# 477ProjectSchematic.net
KiCad netlist of a schematic drawn in EAGLE
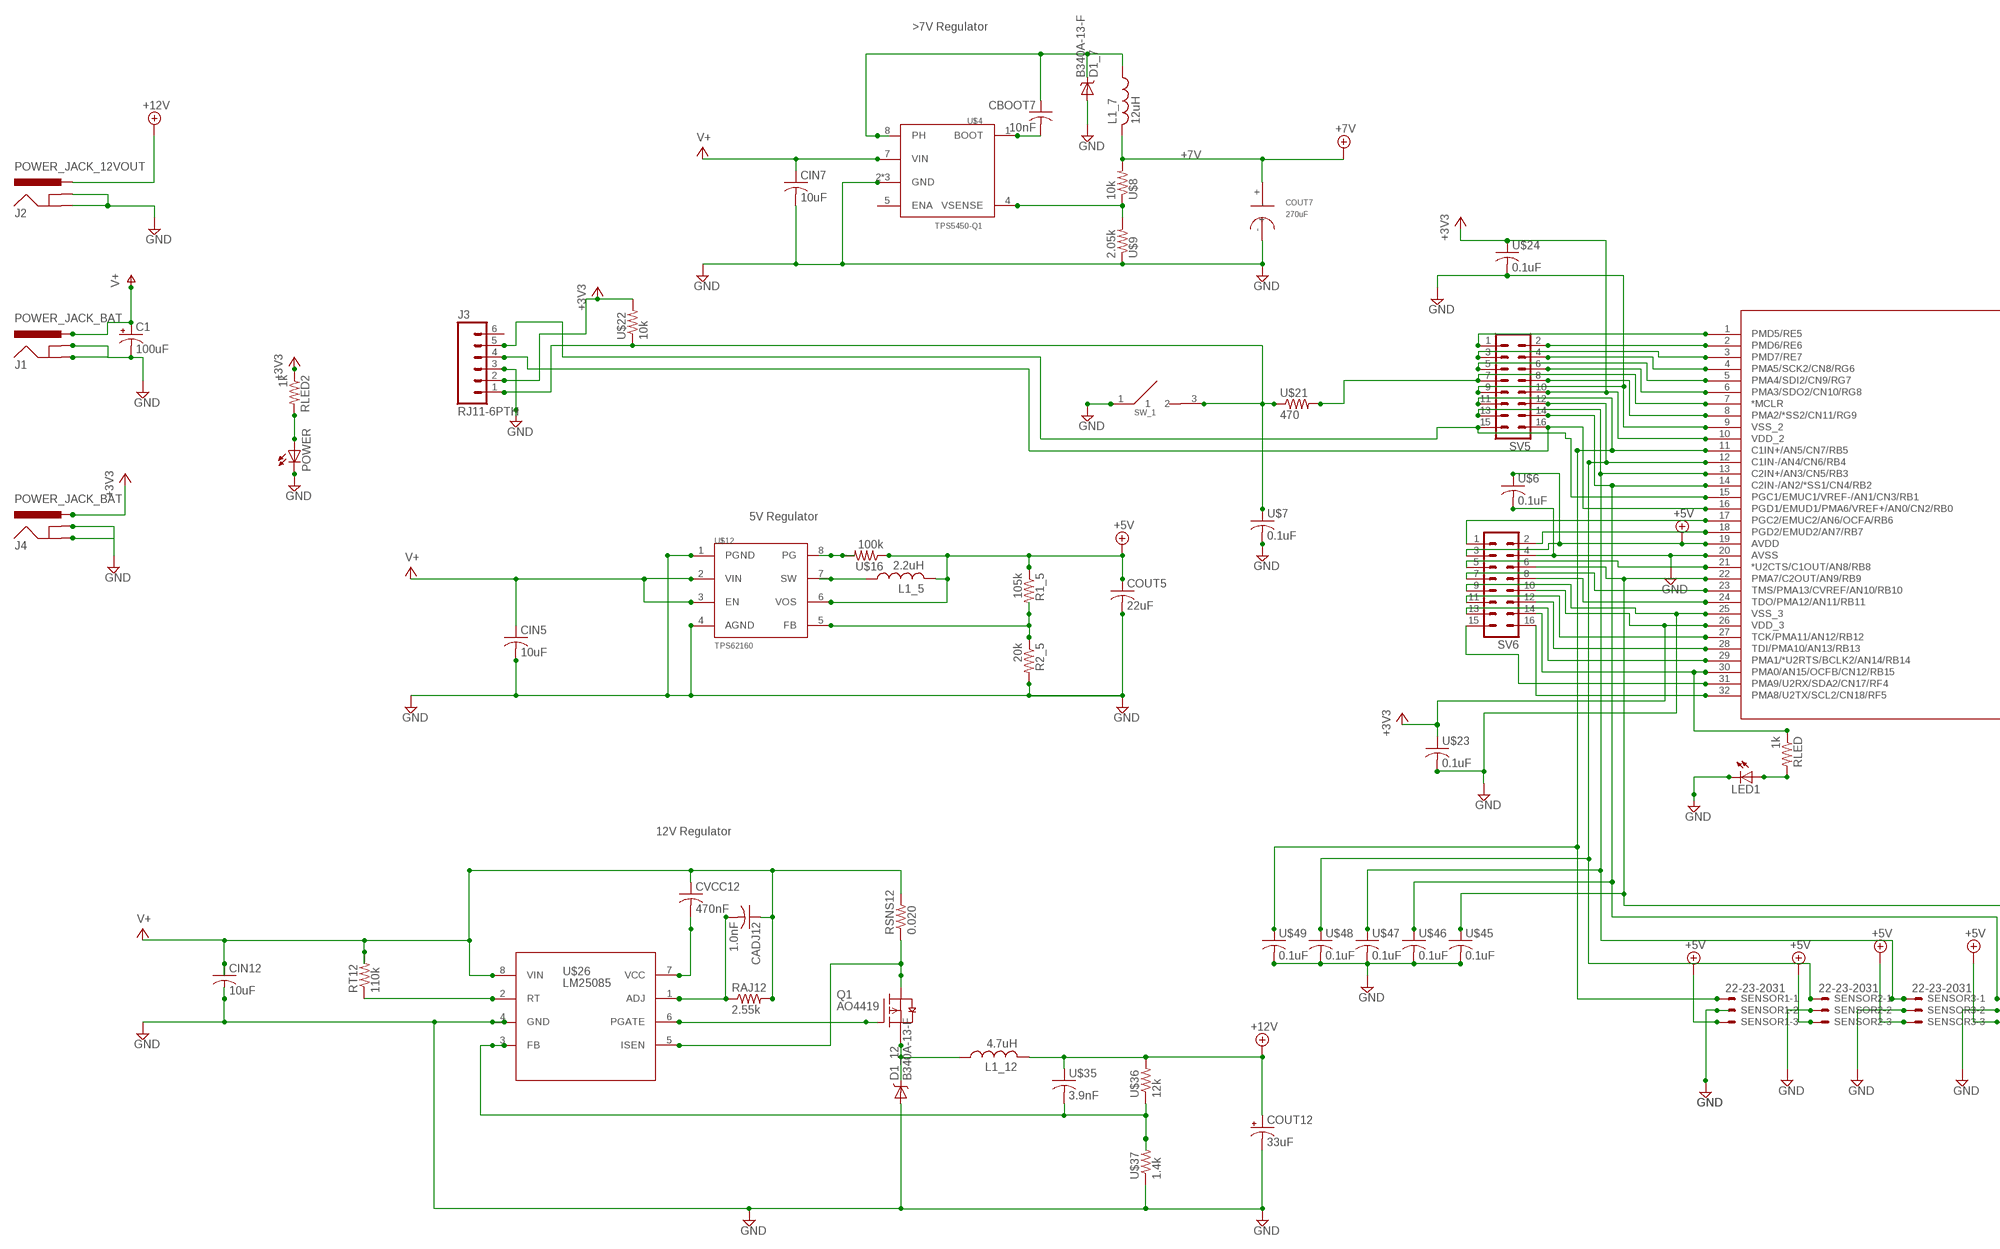
[diagram p0: schematic, sheet 1, part 1 of 2]
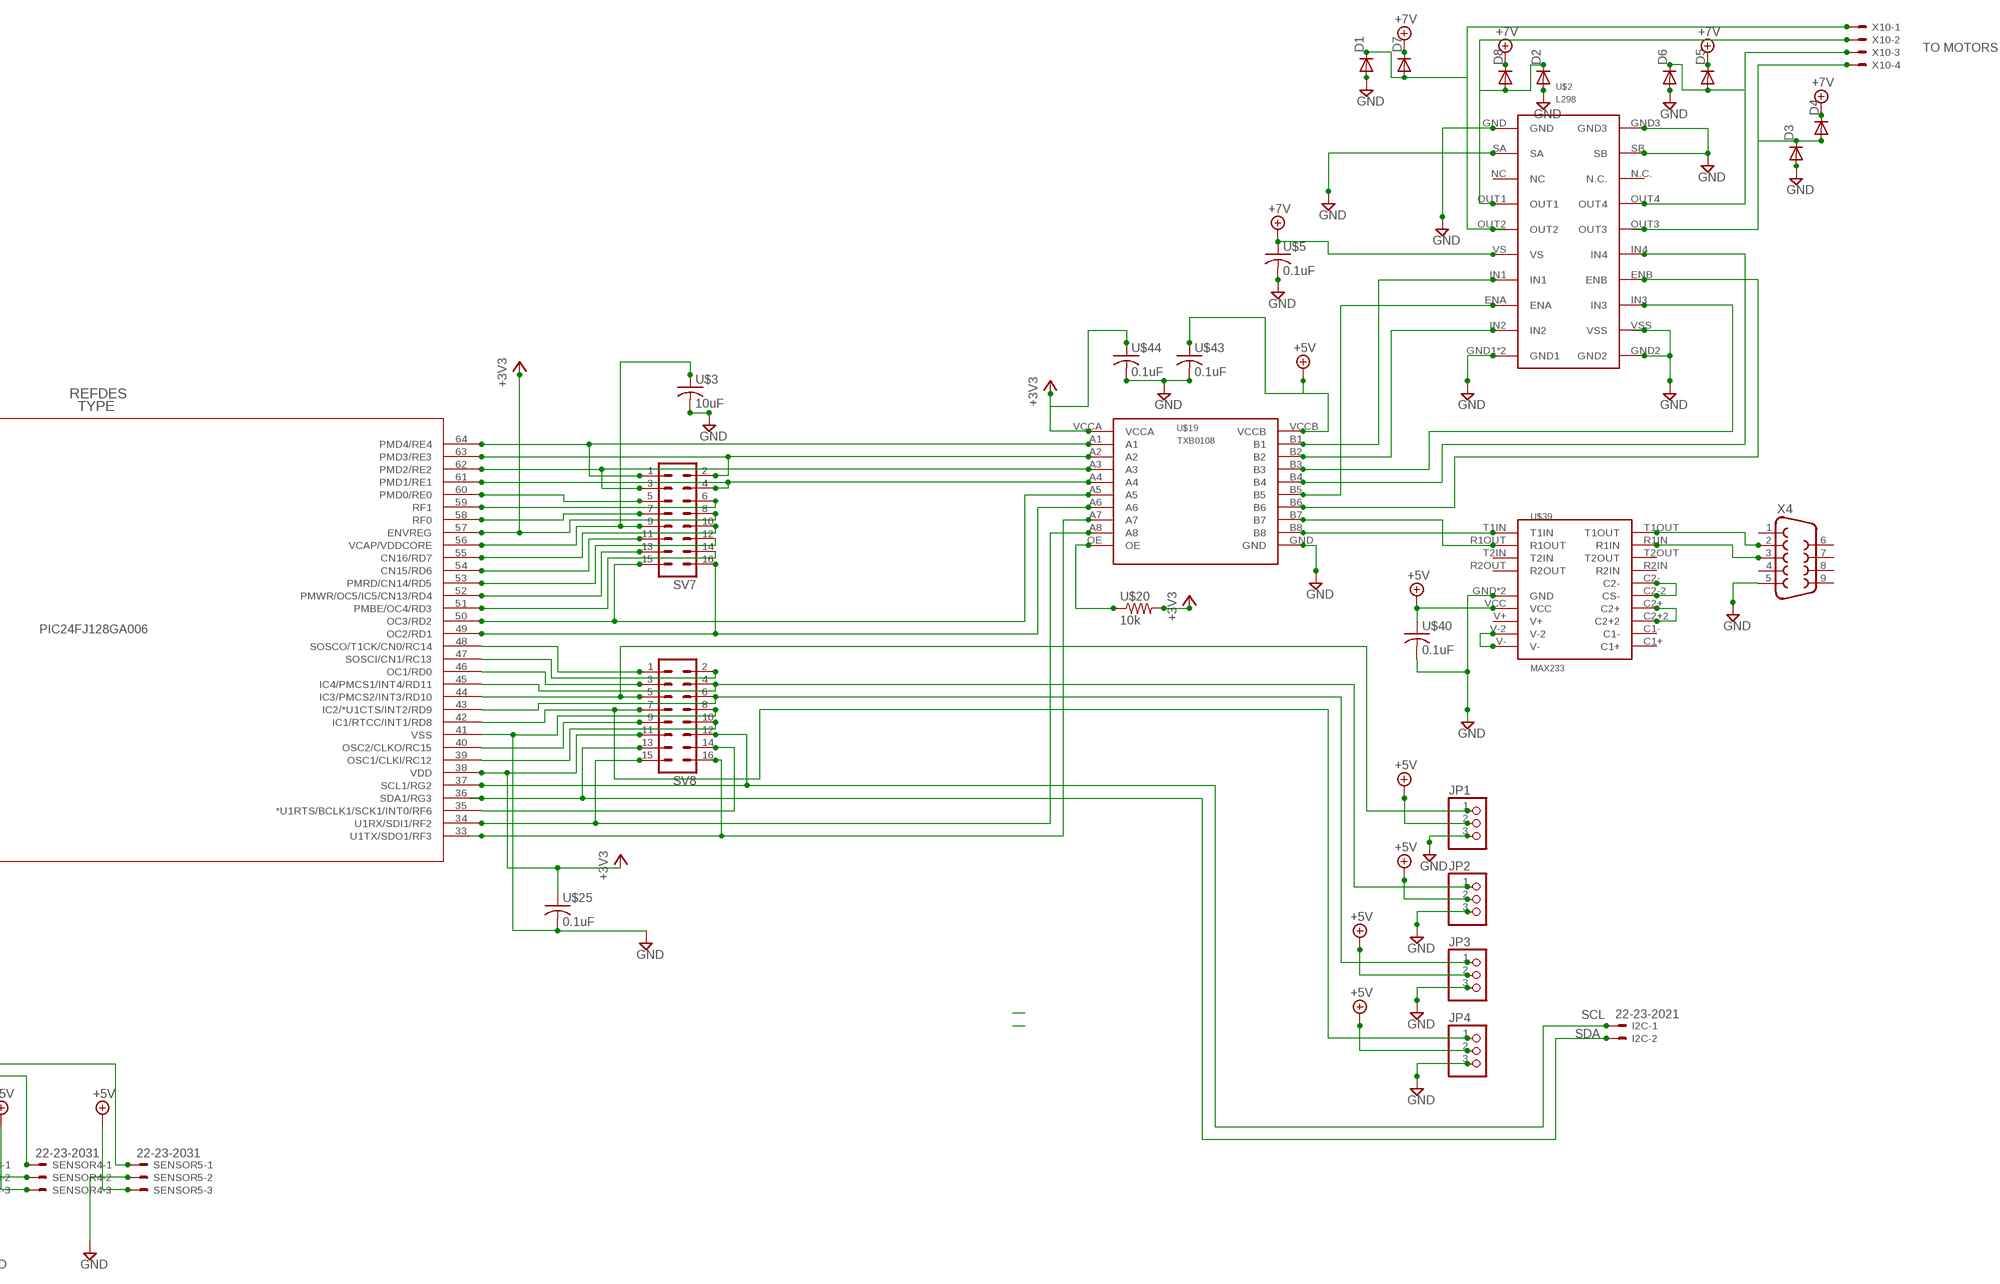
[diagram p1: schematic, sheet 1, part 2 of 2]

(export (version "E")
  (design (tool "Eeschema 10.0.6"))
  (components
    (comp (ref "C1")
      (value "100uF")
      (footprint "eagle-import:E3,5-8")
      (libsource (lib "eagle-import") (part "CPOL-USE3.5-8"))
    )
    (comp (ref "CADJ12")
      (value "1.0nF")
      (footprint "eagle-import:C1206")
      (libsource (lib "eagle-import") (part "C-US-1206"))
    )
    (comp (ref "CBOOT7")
      (value "10nF")
      (footprint "eagle-import:C1206")
      (libsource (lib "eagle-import") (part "C-US-1206"))
    )
    (comp (ref "CIN5")
      (value "10uF")
      (footprint "eagle-import:C1206")
      (libsource (lib "eagle-import") (part "C-US-1206"))
    )
    (comp (ref "CIN7")
      (value "10uF")
      (footprint "eagle-import:C1210")
      (libsource (lib "eagle-import") (part "C-US-1210"))
    )
    (comp (ref "CIN12")
      (value "10uF")
      (footprint "eagle-import:C1210")
      (libsource (lib "eagle-import") (part "C-US-1210"))
    )
    (comp (ref "COUT5")
      (value "22uF")
      (footprint "eagle-import:C1206")
      (libsource (lib "eagle-import") (part "C-US-1206"))
    )
    (comp (ref "COUT7")
      (value "270uF")
      (footprint "eagle-import:CAPSMT_62_J80")
      (libsource (lib "eagle-import") (part "APXA100ARA271MJ80G"))
    )
    (comp (ref "COUT12")
      (value "33uF")
      (footprint "eagle-import:D_7343-31W")
      (libsource (lib "eagle-import") (part "T495D336K025ATE090"))
    )
    (comp (ref "CVCC12")
      (value "470nF")
      (footprint "eagle-import:C1206")
      (libsource (lib "eagle-import") (part "C-US-1206"))
    )
    (comp (ref "D1")
      (value "DIODE-DO-214AC")
      (footprint "eagle-import:DO-214AC")
      (libsource (lib "eagle-import") (part "DIODE-DO-214AC"))
    )
    (comp (ref "D1_7")
      (value "B340A-13-F")
      (footprint "eagle-import:SMA-DIODE")
      (libsource (lib "eagle-import") (part "B340A-13-F"))
    )
    (comp (ref "D1_12")
      (value "B340A-13-F")
      (footprint "eagle-import:SMA-DIODE")
      (libsource (lib "eagle-import") (part "B340A-13-F"))
    )
    (comp (ref "D2")
      (value "DIODE-DO-214AC")
      (footprint "eagle-import:DO-214AC")
      (libsource (lib "eagle-import") (part "DIODE-DO-214AC"))
    )
    (comp (ref "D3")
      (value "DIODE-DO-214AC")
      (footprint "eagle-import:DO-214AC")
      (libsource (lib "eagle-import") (part "DIODE-DO-214AC"))
    )
    (comp (ref "D4")
      (value "DIODE-DO-214AC")
      (footprint "eagle-import:DO-214AC")
      (libsource (lib "eagle-import") (part "DIODE-DO-214AC"))
    )
    (comp (ref "D5")
      (value "DIODE-DO-214AC")
      (footprint "eagle-import:DO-214AC")
      (libsource (lib "eagle-import") (part "DIODE-DO-214AC"))
    )
    (comp (ref "D6")
      (value "DIODE-DO-214AC")
      (footprint "eagle-import:DO-214AC")
      (libsource (lib "eagle-import") (part "DIODE-DO-214AC"))
    )
    (comp (ref "D7")
      (value "DIODE-DO-214AC")
      (footprint "eagle-import:DO-214AC")
      (libsource (lib "eagle-import") (part "DIODE-DO-214AC"))
    )
    (comp (ref "D8")
      (value "DIODE-DO-214AC")
      (footprint "eagle-import:DO-214AC")
      (libsource (lib "eagle-import") (part "DIODE-DO-214AC"))
    )
    (comp (ref "I2C")
      (value "22-23-2021")
      (footprint "eagle-import:22-23-2021")
      (fields (field (name "MF") "MOLEX"))
      (libsource (lib "eagle-import") (part "22-23-2021"))
    )
    (comp (ref "J1")
      (value "POWER_JACK_BAT")
      (footprint "eagle-import:POWER_JACK_PTH")
      (libsource (lib "eagle-import") (part "POWER_JACKPTH"))
    )
    (comp (ref "J2")
      (value "POWER_JACK_12VOUT")
      (footprint "eagle-import:POWER_JACK_PTH")
      (libsource (lib "eagle-import") (part "POWER_JACKPTH"))
    )
    (comp (ref "J3")
      (value "RJ11-6PTH")
      (footprint "eagle-import:RJ11-6")
      (libsource (lib "eagle-import") (part "RJ11-6PTH"))
    )
    (comp (ref "J4")
      (value "POWER_JACK_BAT")
      (footprint "eagle-import:POWER_JACK_PTH")
      (libsource (lib "eagle-import") (part "POWER_JACKPTH"))
    )
    (comp (ref "JP1")
      (value "PINHD-1X3")
      (footprint "eagle-import:1X03")
      (libsource (lib "eagle-import") (part "PINHD-1X3"))
    )
    (comp (ref "JP2")
      (value "PINHD-1X3")
      (footprint "eagle-import:1X03")
      (libsource (lib "eagle-import") (part "PINHD-1X3"))
    )
    (comp (ref "JP3")
      (value "PINHD-1X3")
      (footprint "eagle-import:1X03")
      (libsource (lib "eagle-import") (part "PINHD-1X3"))
    )
    (comp (ref "JP4")
      (value "PINHD-1X3")
      (footprint "eagle-import:1X03")
      (libsource (lib "eagle-import") (part "PINHD-1X3"))
    )
    (comp (ref "L1_5")
      (value "2.2uH")
      (footprint "eagle-import:SDR0403")
      (libsource (lib "eagle-import") (part "SDR0403"))
    )
    (comp (ref "L1_7")
      (value "12uH")
      (footprint "eagle-import:SRR1210")
      (libsource (lib "eagle-import") (part "SRR1210"))
    )
    (comp (ref "L1_12")
      (value "4.7uH")
      (footprint "eagle-import:SLF10165")
      (libsource (lib "eagle-import") (part "SLF10165T-4R7N4R73PF"))
    )
    (comp (ref "LED1")
      (value "LEDSMT1206")
      (footprint "eagle-import:1206")
      (libsource (lib "eagle-import") (part "LEDSMT1206"))
    )
    (comp (ref "POWER")
      (value "LEDSMT1206")
      (footprint "eagle-import:1206")
      (libsource (lib "eagle-import") (part "LEDSMT1206"))
    )
    (comp (ref "Q1")
      (value "AO4419")
      (footprint "eagle-import:SOIC8")
      (libsource (lib "eagle-import") (part "AO4419"))
    )
    (comp (ref "R1_5")
      (value "105k")
      (footprint "eagle-import:R1206")
      (libsource (lib "eagle-import") (part "R-US{dblquote}"))
    )
    (comp (ref "R2_5")
      (value "20k")
      (footprint "eagle-import:R1206")
      (libsource (lib "eagle-import") (part "R-US{dblquote}"))
    )
    (comp (ref "RAJ12")
      (value "2.55k")
      (footprint "eagle-import:R1206")
      (libsource (lib "eagle-import") (part "R-US{dblquote}"))
    )
    (comp (ref "RLED")
      (value "1k")
      (footprint "eagle-import:R1206")
      (libsource (lib "eagle-import") (part "R-US{dblquote}"))
    )
    (comp (ref "RLED2")
      (value "1k")
      (footprint "eagle-import:R1206")
      (libsource (lib "eagle-import") (part "R-US{dblquote}"))
    )
    (comp (ref "RSNS12")
      (value "0.020")
      (footprint "eagle-import:R1206")
      (libsource (lib "eagle-import") (part "R-US{dblquote}"))
    )
    (comp (ref "RT12")
      (value "110k")
      (footprint "eagle-import:R1206")
      (libsource (lib "eagle-import") (part "R-US{dblquote}"))
    )
    (comp (ref "SENSOR1")
      (value "22-23-2031")
      (footprint "eagle-import:22-23-2031")
      (fields (field (name "MF") "MOLEX"))
      (libsource (lib "eagle-import") (part "22-23-2031"))
    )
    (comp (ref "SENSOR2")
      (value "22-23-2031")
      (footprint "eagle-import:22-23-2031")
      (fields (field (name "MF") "MOLEX"))
      (libsource (lib "eagle-import") (part "22-23-2031"))
    )
    (comp (ref "SENSOR3")
      (value "22-23-2031")
      (footprint "eagle-import:22-23-2031")
      (fields (field (name "MF") "MOLEX"))
      (libsource (lib "eagle-import") (part "22-23-2031"))
    )
    (comp (ref "SENSOR4")
      (value "22-23-2031")
      (footprint "eagle-import:22-23-2031")
      (fields (field (name "MF") "MOLEX"))
      (libsource (lib "eagle-import") (part "22-23-2031"))
    )
    (comp (ref "SENSOR5")
      (value "22-23-2031")
      (footprint "eagle-import:22-23-2031")
      (fields (field (name "MF") "MOLEX"))
      (libsource (lib "eagle-import") (part "22-23-2031"))
    )
    (comp (ref "SV5")
      (value "MA08-2")
      (footprint "eagle-import:MA08-2")
      (libsource (lib "eagle-import") (part "MA08-2"))
    )
    (comp (ref "SV6")
      (value "MA08-2")
      (footprint "eagle-import:MA08-2")
      (libsource (lib "eagle-import") (part "MA08-2"))
    )
    (comp (ref "SV7")
      (value "MA08-2")
      (footprint "eagle-import:MA08-2")
      (libsource (lib "eagle-import") (part "MA08-2"))
    )
    (comp (ref "SV8")
      (value "MA08-2")
      (footprint "eagle-import:MA08-2")
      (libsource (lib "eagle-import") (part "MA08-2"))
    )
    (comp (ref "SW_1")
      (value "RESET_BUTTON")
      (footprint "eagle-import:TACTILE-PTH-12MM")
      (libsource (lib "eagle-import") (part "RESET_BUTTON"))
    )
    (comp (ref "U$1")
      (value "PIC24FJ128GA006-")
      (footprint "eagle-import:TQFP64_10X10MC")
      (libsource (lib "eagle-import") (part "PIC24FJ128GA006-"))
    )
    (comp (ref "U$2")
      (value "L298")
      (footprint "eagle-import:L298")
      (libsource (lib "eagle-import") (part "L298"))
    )
    (comp (ref "U$3")
      (value "10uF")
      (footprint "eagle-import:C1206")
      (libsource (lib "eagle-import") (part "C-US-1206"))
    )
    (comp (ref "U$4")
      (value "TPS5450-Q1")
      (footprint "eagle-import:PSOP-8")
      (libsource (lib "eagle-import") (part "TPS5450-Q1"))
    )
    (comp (ref "U$5")
      (value "0.1uF")
      (footprint "eagle-import:C1206")
      (libsource (lib "eagle-import") (part "C-US-1206"))
    )
    (comp (ref "U$6")
      (value "0.1uF")
      (footprint "eagle-import:C1206")
      (libsource (lib "eagle-import") (part "C-US-1206"))
    )
    (comp (ref "U$7")
      (value "0.1uF")
      (footprint "eagle-import:C1206")
      (libsource (lib "eagle-import") (part "C-US-1206"))
    )
    (comp (ref "U$8")
      (value "10k")
      (footprint "eagle-import:R1206")
      (libsource (lib "eagle-import") (part "R-US{dblquote}"))
    )
    (comp (ref "U$9")
      (value "2.05k")
      (footprint "eagle-import:R1206")
      (libsource (lib "eagle-import") (part "R-US{dblquote}"))
    )
    (comp (ref "U$12")
      (value "TPS62160")
      (footprint "eagle-import:MSOP-8")
      (libsource (lib "eagle-import") (part "TPS62160"))
    )
    (comp (ref "U$16")
      (value "100k")
      (footprint "eagle-import:R1206")
      (libsource (lib "eagle-import") (part "R-US{dblquote}"))
    )
    (comp (ref "U$19")
      (value "TXB0108")
      (footprint "eagle-import:TXB0108")
      (libsource (lib "eagle-import") (part "TXB0108"))
    )
    (comp (ref "U$20")
      (value "10k")
      (footprint "eagle-import:R1206")
      (libsource (lib "eagle-import") (part "R-US{dblquote}"))
    )
    (comp (ref "U$21")
      (value "470")
      (footprint "eagle-import:R1206")
      (libsource (lib "eagle-import") (part "R-US{dblquote}"))
    )
    (comp (ref "U$22")
      (value "10k")
      (footprint "eagle-import:R1206")
      (libsource (lib "eagle-import") (part "R-US{dblquote}"))
    )
    (comp (ref "U$23")
      (value "0.1uF")
      (footprint "eagle-import:C1206")
      (libsource (lib "eagle-import") (part "C-US-1206"))
    )
    (comp (ref "U$24")
      (value "0.1uF")
      (footprint "eagle-import:C1206")
      (libsource (lib "eagle-import") (part "C-US-1206"))
    )
    (comp (ref "U$25")
      (value "0.1uF")
      (footprint "eagle-import:C1206")
      (libsource (lib "eagle-import") (part "C-US-1206"))
    )
    (comp (ref "U$26")
      (value "LM25085")
      (footprint "eagle-import:MSOP-8")
      (libsource (lib "eagle-import") (part "LM25085"))
    )
    (comp (ref "U$35")
      (value "3.9nF")
      (footprint "eagle-import:C1206")
      (libsource (lib "eagle-import") (part "C-US-1206"))
    )
    (comp (ref "U$36")
      (value "12k")
      (footprint "eagle-import:R1206")
      (libsource (lib "eagle-import") (part "R-US{dblquote}"))
    )
    (comp (ref "U$37")
      (value "1.4k")
      (footprint "eagle-import:R1206")
      (libsource (lib "eagle-import") (part "R-US{dblquote}"))
    )
    (comp (ref "U$39")
      (value "MAX233")
      (footprint "eagle-import:SOIC-20")
      (libsource (lib "eagle-import") (part "MAX233"))
    )
    (comp (ref "U$40")
      (value "0.1uF")
      (footprint "eagle-import:C1206")
      (libsource (lib "eagle-import") (part "C-US-1206"))
    )
    (comp (ref "U$43")
      (value "0.1uF")
      (footprint "eagle-import:C1206")
      (libsource (lib "eagle-import") (part "C-US-1206"))
    )
    (comp (ref "U$44")
      (value "0.1uF")
      (footprint "eagle-import:C1206")
      (libsource (lib "eagle-import") (part "C-US-1206"))
    )
    (comp (ref "U$45")
      (value "0.1uF")
      (footprint "eagle-import:C1206")
      (libsource (lib "eagle-import") (part "C-US-1206"))
    )
    (comp (ref "U$46")
      (value "0.1uF")
      (footprint "eagle-import:C1206")
      (libsource (lib "eagle-import") (part "C-US-1206"))
    )
    (comp (ref "U$47")
      (value "0.1uF")
      (footprint "eagle-import:C1206")
      (libsource (lib "eagle-import") (part "C-US-1206"))
    )
    (comp (ref "U$48")
      (value "0.1uF")
      (footprint "eagle-import:C1206")
      (libsource (lib "eagle-import") (part "C-US-1206"))
    )
    (comp (ref "U$49")
      (value "0.1uF")
      (footprint "eagle-import:C1206")
      (libsource (lib "eagle-import") (part "C-US-1206"))
    )
    (comp (ref "X4")
      (value "DB9FEMALE")
      (footprint "eagle-import:DB9")
      (libsource (lib "eagle-import") (part "DB9FEMALE"))
    )
    (comp (ref "X10")
      (value "22-23-2041")
      (footprint "eagle-import:22-23-2041")
      (fields (field (name "MF") "MOLEX"))
      (libsource (lib "eagle-import") (part "22-23-2041"))
    )
  )
  (nets
    (net (code "1") (name "+3V3") (class "Default")
      (node (ref "J3") (pin "2") (pinfunction "2_2") (pintype "passive"))
      (node (ref "J4") (pin "PWR") (pinfunction "PWR_PWR") (pintype "bidirectional"))
      (node (ref "RLED2") (pin "1") (pinfunction "1_1") (pintype "passive"))
      (node (ref "SV5") (pin "10") (pinfunction "10_10") (pintype "passive"))
      (node (ref "SV6") (pin "10") (pinfunction "10_10") (pintype "passive"))
      (node (ref "SV7") (pin "8") (pinfunction "8_8") (pintype "passive"))
      (node (ref "SV8") (pin "11") (pinfunction "11_11") (pintype "passive"))
      (node (ref "U$1") (pin "10") (pinfunction "VDD_2_10") (pintype "passive"))
      (node (ref "U$1") (pin "26") (pinfunction "VDD_3_26") (pintype "passive"))
      (node (ref "U$1") (pin "38") (pinfunction "VDD_38") (pintype "passive"))
      (node (ref "U$1") (pin "57") (pinfunction "ENVREG_57") (pintype "passive"))
      (node (ref "U$19") (pin "VCCA") (pinfunction "VCCA_VCCA") (pintype "bidirectional"))
      (node (ref "U$20") (pin "2") (pinfunction "2_2") (pintype "passive"))
      (node (ref "U$22") (pin "2") (pinfunction "2_2") (pintype "passive"))
      (node (ref "U$23") (pin "1") (pinfunction "1_1") (pintype "passive"))
      (node (ref "U$24") (pin "1") (pinfunction "1_1") (pintype "passive"))
      (node (ref "U$25") (pin "1") (pinfunction "1_1") (pintype "passive"))
      (node (ref "U$44") (pin "1") (pinfunction "1_1") (pintype "passive"))
    )
    (net (code "2") (name "+5V") (class "Default")
      (node (ref "COUT5") (pin "1") (pinfunction "1_1") (pintype "passive"))
      (node (ref "JP1") (pin "2") (pinfunction "2_2") (pintype "passive"))
      (node (ref "JP2") (pin "2") (pinfunction "2_2") (pintype "passive"))
      (node (ref "JP3") (pin "2") (pinfunction "2_2") (pintype "passive"))
      (node (ref "JP4") (pin "2") (pinfunction "2_2") (pintype "passive"))
      (node (ref "L1_5") (pin "B") (pinfunction "2_B") (pintype "passive"))
      (node (ref "R1_5") (pin "1") (pinfunction "1_1") (pintype "passive"))
      (node (ref "SENSOR1") (pin "3") (pinfunction "S_3") (pintype "passive"))
      (node (ref "SENSOR2") (pin "3") (pinfunction "S_3") (pintype "passive"))
      (node (ref "SENSOR3") (pin "3") (pinfunction "S_3") (pintype "passive"))
      (node (ref "SENSOR4") (pin "3") (pinfunction "S_3") (pintype "passive"))
      (node (ref "SENSOR5") (pin "3") (pinfunction "S_3") (pintype "passive"))
      (node (ref "SV6") (pin "3") (pinfunction "3_3") (pintype "passive"))
      (node (ref "U$1") (pin "19") (pinfunction "AVDD_19") (pintype "passive"))
      (node (ref "U$12") (pin "6") (pinfunction "VOS_6") (pintype "bidirectional"))
      (node (ref "U$16") (pin "1") (pinfunction "1_1") (pintype "passive"))
      (node (ref "U$19") (pin "VCCB") (pinfunction "VCCB_VCCB") (pintype "bidirectional"))
      (node (ref "U$39") (pin "VCC") (pinfunction "VCC_VCC") (pintype "bidirectional"))
      (node (ref "U$40") (pin "1") (pinfunction "1_1") (pintype "passive"))
      (node (ref "U$43") (pin "1") (pinfunction "1_1") (pintype "passive"))
      (node (ref "U$6") (pin "1") (pinfunction "1_1") (pintype "passive"))
    )
    (net (code "3") (name "+7V") (class "Default")
      (node (ref "COUT7") (pin "+") (pinfunction "+_+") (pintype "bidirectional"))
      (node (ref "D4") (pin "C") (pinfunction "C_C") (pintype "passive"))
      (node (ref "D5") (pin "C") (pinfunction "C_C") (pintype "passive"))
      (node (ref "D7") (pin "C") (pinfunction "C_C") (pintype "passive"))
      (node (ref "D8") (pin "C") (pinfunction "C_C") (pintype "passive"))
      (node (ref "L1_7") (pin "B") (pinfunction "2_B") (pintype "passive"))
      (node (ref "U$2") (pin "VS") (pinfunction "VS_VS") (pintype "bidirectional"))
      (node (ref "U$5") (pin "1") (pinfunction "1_1") (pintype "passive"))
      (node (ref "U$8") (pin "2") (pinfunction "2_2") (pintype "passive"))
    )
    (net (code "4") (name "+12V") (class "Default")
      (node (ref "COUT12") (pin "+") (pinfunction "+_+") (pintype "passive"))
      (node (ref "J2") (pin "PWR") (pinfunction "PWR_PWR") (pintype "bidirectional"))
      (node (ref "L1_12") (pin "2") (pinfunction "2_2") (pintype "passive"))
      (node (ref "U$35") (pin "1") (pinfunction "1_1") (pintype "passive"))
      (node (ref "U$36") (pin "2") (pinfunction "2_2") (pintype "passive"))
    )
    (net (code "5") (name "GND") (class "Default")
      (node (ref "C1") (pin "-") (pinfunction "-_-") (pintype "passive"))
      (node (ref "CIN12") (pin "2") (pinfunction "2_2") (pintype "passive"))
      (node (ref "CIN5") (pin "2") (pinfunction "2_2") (pintype "passive"))
      (node (ref "CIN7") (pin "2") (pinfunction "2_2") (pintype "passive"))
      (node (ref "COUT12") (pin "-") (pinfunction "-_-") (pintype "passive"))
      (node (ref "COUT5") (pin "2") (pinfunction "2_2") (pintype "passive"))
      (node (ref "COUT7") (pin "-") (pinfunction "-_-") (pintype "bidirectional"))
      (node (ref "D1") (pin "A") (pinfunction "A_A") (pintype "passive"))
      (node (ref "D1_12") (pin "-") (pinfunction "-_-") (pintype "passive"))
      (node (ref "D1_7") (pin "-") (pinfunction "-_-") (pintype "passive"))
      (node (ref "D2") (pin "A") (pinfunction "A_A") (pintype "passive"))
      (node (ref "D3") (pin "A") (pinfunction "A_A") (pintype "passive"))
      (node (ref "D6") (pin "A") (pinfunction "A_A") (pintype "passive"))
      (node (ref "J1") (pin "GND") (pinfunction "GND_GND") (pintype "bidirectional"))
      (node (ref "J1") (pin "GNDBREAK") (pinfunction "GNDBREAK_GNDBREAK") (pintype "bidirectional"))
      (node (ref "J2") (pin "GND") (pinfunction "GND_GND") (pintype "bidirectional"))
      (node (ref "J2") (pin "GNDBREAK") (pinfunction "GNDBREAK_GNDBREAK") (pintype "bidirectional"))
      (node (ref "J3") (pin "3") (pinfunction "3_3") (pintype "passive"))
      (node (ref "J4") (pin "GND") (pinfunction "GND_GND") (pintype "bidirectional"))
      (node (ref "J4") (pin "GNDBREAK") (pinfunction "GNDBREAK_GNDBREAK") (pintype "bidirectional"))
      (node (ref "JP1") (pin "3") (pinfunction "3_3") (pintype "passive"))
      (node (ref "JP2") (pin "3") (pinfunction "3_3") (pintype "passive"))
      (node (ref "JP3") (pin "3") (pinfunction "3_3") (pintype "passive"))
      (node (ref "JP4") (pin "3") (pinfunction "3_3") (pintype "passive"))
      (node (ref "LED1") (pin "C") (pinfunction "C_C") (pintype "passive"))
      (node (ref "POWER") (pin "C") (pinfunction "C_C") (pintype "passive"))
      (node (ref "R2_5") (pin "2") (pinfunction "2_2") (pintype "passive"))
      (node (ref "SENSOR1") (pin "2") (pinfunction "S_2") (pintype "passive"))
      (node (ref "SENSOR2") (pin "2") (pinfunction "S_2") (pintype "passive"))
      (node (ref "SENSOR3") (pin "2") (pinfunction "S_2") (pintype "passive"))
      (node (ref "SENSOR4") (pin "2") (pinfunction "S_2") (pintype "passive"))
      (node (ref "SENSOR5") (pin "2") (pinfunction "S_2") (pintype "passive"))
      (node (ref "SV5") (pin "9") (pinfunction "9_9") (pintype "passive"))
      (node (ref "SV6") (pin "4") (pinfunction "4_4") (pintype "passive"))
      (node (ref "SV6") (pin "9") (pinfunction "9_9") (pintype "passive"))
      (node (ref "SV8") (pin "8") (pinfunction "8_8") (pintype "passive"))
      (node (ref "SW_1") (pin "1") (pinfunction "1_1") (pintype "bidirectional"))
      (node (ref "U$1") (pin "20") (pinfunction "AVSS_20") (pintype "passive"))
      (node (ref "U$1") (pin "25") (pinfunction "VSS_3_25") (pintype "passive"))
      (node (ref "U$1") (pin "41") (pinfunction "VSS_41") (pintype "passive"))
      (node (ref "U$1") (pin "9") (pinfunction "VSS_2_9") (pintype "passive"))
      (node (ref "U$12") (pin "1") (pinfunction "PGND_1") (pintype "bidirectional"))
      (node (ref "U$12") (pin "4") (pinfunction "AGND_4") (pintype "bidirectional"))
      (node (ref "U$19") (pin "GND") (pinfunction "GND_GND") (pintype "bidirectional"))
      (node (ref "U$2") (pin "GND") (pinfunction "GND_GND") (pintype "bidirectional"))
      (node (ref "U$2") (pin "GND1") (pinfunction "GND1_GND1") (pintype "bidirectional"))
      (node (ref "U$2") (pin "GND2") (pinfunction "GND2_GND2") (pintype "bidirectional"))
      (node (ref "U$2") (pin "GND3") (pinfunction "GND3_GND3") (pintype "bidirectional"))
      (node (ref "U$2") (pin "GNDPAD") (pinfunction "GND1_GNDPAD") (pintype "bidirectional"))
      (node (ref "U$2") (pin "SA") (pinfunction "SA_SA") (pintype "bidirectional"))
      (node (ref "U$2") (pin "SB") (pinfunction "SB_SB") (pintype "bidirectional"))
      (node (ref "U$2") (pin "VSS") (pinfunction "VSS_VSS") (pintype "bidirectional"))
      (node (ref "U$23") (pin "2") (pinfunction "2_2") (pintype "passive"))
      (node (ref "U$24") (pin "2") (pinfunction "2_2") (pintype "passive"))
      (node (ref "U$25") (pin "2") (pinfunction "2_2") (pintype "passive"))
      (node (ref "U$26") (pin "4") (pinfunction "GND_4") (pintype "bidirectional"))
      (node (ref "U$3") (pin "2") (pinfunction "2_2") (pintype "passive"))
      (node (ref "U$37") (pin "1") (pinfunction "1_1") (pintype "passive"))
      (node (ref "U$39") (pin "GND") (pinfunction "GND_GND") (pintype "bidirectional"))
      (node (ref "U$39") (pin "GND2") (pinfunction "GND_GND2") (pintype "bidirectional"))
      (node (ref "U$4") (pin "2") (pinfunction "GND_2") (pintype "bidirectional"))
      (node (ref "U$4") (pin "6") (pinfunction "GND_6") (pintype "bidirectional"))
      (node (ref "U$4") (pin "PAD") (pinfunction "GND_PAD") (pintype "bidirectional"))
      (node (ref "U$40") (pin "2") (pinfunction "2_2") (pintype "passive"))
      (node (ref "U$43") (pin "2") (pinfunction "2_2") (pintype "passive"))
      (node (ref "U$44") (pin "2") (pinfunction "2_2") (pintype "passive"))
      (node (ref "U$45") (pin "2") (pinfunction "2_2") (pintype "passive"))
      (node (ref "U$46") (pin "2") (pinfunction "2_2") (pintype "passive"))
      (node (ref "U$47") (pin "2") (pinfunction "2_2") (pintype "passive"))
      (node (ref "U$48") (pin "2") (pinfunction "2_2") (pintype "passive"))
      (node (ref "U$49") (pin "2") (pinfunction "2_2") (pintype "passive"))
      (node (ref "U$5") (pin "2") (pinfunction "2_2") (pintype "passive"))
      (node (ref "U$6") (pin "2") (pinfunction "2_2") (pintype "passive"))
      (node (ref "U$7") (pin "2") (pinfunction "2_2") (pintype "passive"))
      (node (ref "U$9") (pin "1") (pinfunction "1_1") (pintype "passive"))
      (node (ref "X4") (pin "5") (pinfunction "5_5") (pintype "passive"))
    )
    (net (code "6") (name "Net-(D1_12-Pad+)") (class "Default")
      (node (ref "D1_12") (pin "+") (pinfunction "+_+") (pintype "passive"))
      (node (ref "L1_12") (pin "1") (pinfunction "1_1") (pintype "passive"))
      (node (ref "Q1") (pin "1") (pinfunction "S_1") (pintype "passive"))
      (node (ref "Q1") (pin "2") (pinfunction "S_2") (pintype "passive"))
      (node (ref "Q1") (pin "3") (pinfunction "S_3") (pintype "passive"))
    )
    (net (code "7") (name "Net-(I2CA-S)") (class "Default")
      (node (ref "I2C") (pin "1") (pinfunction "S_1") (pintype "passive"))
      (node (ref "SV8") (pin "12") (pinfunction "12_12") (pintype "passive"))
      (node (ref "U$1") (pin "37") (pinfunction "SCL1/RG2_37") (pintype "passive"))
    )
    (net (code "8") (name "Net-(I2CB-S)") (class "Default")
      (node (ref "I2C") (pin "2") (pinfunction "S_2") (pintype "passive"))
      (node (ref "SV8") (pin "13") (pinfunction "13_13") (pintype "passive"))
      (node (ref "U$1") (pin "36") (pinfunction "SDA1/RG3_36") (pintype "passive"))
    )
    (net (code "9") (name "Net-(L1_5-1)") (class "Default")
      (node (ref "L1_5") (pin "A") (pinfunction "1_A") (pintype "passive"))
      (node (ref "U$12") (pin "7") (pinfunction "SW_7") (pintype "bidirectional"))
    )
    (net (code "10") (name "Net-(L1_7-1)") (class "Default")
      (node (ref "CBOOT7") (pin "1") (pinfunction "1_1") (pintype "passive"))
      (node (ref "D1_7") (pin "+") (pinfunction "+_+") (pintype "passive"))
      (node (ref "L1_7") (pin "A") (pinfunction "1_A") (pintype "passive"))
      (node (ref "U$4") (pin "8") (pinfunction "PH_8") (pintype "bidirectional"))
    )
    (net (code "11") (name "Net-(LED1-PadA)") (class "Default")
      (node (ref "LED1") (pin "A") (pinfunction "A_A") (pintype "passive"))
      (node (ref "RLED") (pin "2") (pinfunction "2_2") (pintype "passive"))
    )
    (net (code "12") (name "Net-(POWER-PadA)") (class "Default")
      (node (ref "POWER") (pin "A") (pinfunction "A_A") (pintype "passive"))
      (node (ref "RLED2") (pin "2") (pinfunction "2_2") (pintype "passive"))
    )
    (net (code "13") (name "Net-(Q1-G)") (class "Default")
      (node (ref "Q1") (pin "4") (pinfunction "G_4") (pintype "passive"))
      (node (ref "U$26") (pin "6") (pinfunction "PGATE_6") (pintype "bidirectional"))
    )
    (net (code "14") (name "Net-(SENSOR1A-S)") (class "Default")
      (node (ref "SENSOR1") (pin "1") (pinfunction "S_1") (pintype "passive"))
      (node (ref "SV5") (pin "11") (pinfunction "11_11") (pintype "passive"))
      (node (ref "U$1") (pin "11") (pinfunction "C1IN+/AN5/CN7/RB5_11") (pintype "passive"))
      (node (ref "U$49") (pin "1") (pinfunction "1_1") (pintype "passive"))
    )
    (net (code "15") (name "Net-(SENSOR2A-S)") (class "Default")
      (node (ref "SENSOR2") (pin "1") (pinfunction "S_1") (pintype "passive"))
      (node (ref "SV5") (pin "12") (pinfunction "12_12") (pintype "passive"))
      (node (ref "U$1") (pin "12") (pinfunction "C1IN-/AN4/CN6/RB4_12") (pintype "passive"))
      (node (ref "U$48") (pin "1") (pinfunction "1_1") (pintype "passive"))
    )
    (net (code "16") (name "Net-(SENSOR3A-S)") (class "Default")
      (node (ref "SENSOR3") (pin "1") (pinfunction "S_1") (pintype "passive"))
      (node (ref "SV5") (pin "13") (pinfunction "13_13") (pintype "passive"))
      (node (ref "U$1") (pin "13") (pinfunction "C2IN+/AN3/CN5/RB3_13") (pintype "passive"))
      (node (ref "U$47") (pin "1") (pinfunction "1_1") (pintype "passive"))
    )
    (net (code "17") (name "Net-(SENSOR4A-S)") (class "Default")
      (node (ref "SENSOR4") (pin "1") (pinfunction "S_1") (pintype "passive"))
      (node (ref "SV5") (pin "14") (pinfunction "14_14") (pintype "passive"))
      (node (ref "U$1") (pin "14") (pinfunction "C2IN-/AN2/*SS1/CN4/RB2_14") (pintype "passive"))
      (node (ref "U$46") (pin "1") (pinfunction "1_1") (pintype "passive"))
    )
    (net (code "18") (name "Net-(SENSOR5A-S)") (class "Default")
      (node (ref "SENSOR5") (pin "1") (pinfunction "S_1") (pintype "passive"))
      (node (ref "SV6") (pin "6") (pinfunction "6_6") (pintype "passive"))
      (node (ref "U$1") (pin "22") (pinfunction "PMA7/C2OUT/AN9/RB9_22") (pintype "passive"))
      (node (ref "U$45") (pin "1") (pinfunction "1_1") (pintype "passive"))
    )
    (net (code "19") (name "Net-(SW_1-2)") (class "Default")
      (node (ref "J3") (pin "1") (pinfunction "1_1") (pintype "passive"))
      (node (ref "SW_1") (pin "3") (pinfunction "2_3") (pintype "bidirectional"))
      (node (ref "U$21") (pin "1") (pinfunction "1_1") (pintype "passive"))
      (node (ref "U$22") (pin "1") (pinfunction "1_1") (pintype "passive"))
      (node (ref "U$7") (pin "1") (pinfunction "1_1") (pintype "passive"))
    )
    (net (code "20") (name "Net-(U$1-*MCLR)") (class "Default")
      (node (ref "SV5") (pin "7") (pinfunction "7_7") (pintype "passive"))
      (node (ref "U$1") (pin "7") (pinfunction "*MCLR_7") (pintype "passive"))
      (node (ref "U$21") (pin "2") (pinfunction "2_2") (pintype "passive"))
    )
    (net (code "21") (name "Net-(U$1-*U1RTS{slash}BCLK1{slash}SCK1{slash}INT0{slash}RF6)") (class "Default")
      (node (ref "SV8") (pin "14") (pinfunction "14_14") (pintype "passive"))
      (node (ref "U$1") (pin "35") (pinfunction "*U1RTS/BCLK1/SCK1/INT0/RF6_35") (pintype "passive"))
    )
    (net (code "22") (name "Net-(U$1-*U2CTS{slash}C1OUT{slash}AN8{slash}RB8)") (class "Default")
      (node (ref "SV6") (pin "5") (pinfunction "5_5") (pintype "passive"))
      (node (ref "U$1") (pin "21") (pinfunction "*U2CTS/C1OUT/AN8/RB8_21") (pintype "passive"))
    )
    (net (code "23") (name "Net-(U$1-CN15{slash}RD6)") (class "Default")
      (node (ref "SV7") (pin "11") (pinfunction "11_11") (pintype "passive"))
      (node (ref "U$1") (pin "54") (pinfunction "CN15/RD6_54") (pintype "passive"))
    )
    (net (code "24") (name "Net-(U$1-CN16{slash}RD7)") (class "Default")
      (node (ref "SV7") (pin "10") (pinfunction "10_10") (pintype "passive"))
      (node (ref "U$1") (pin "55") (pinfunction "CN16/RD7_55") (pintype "passive"))
    )
    (net (code "25") (name "Net-(U$1-IC1{slash}RTCC{slash}INT1{slash}RD8)") (class "Default")
      (node (ref "JP4") (pin "1") (pinfunction "1_1") (pintype "passive"))
      (node (ref "SV8") (pin "7") (pinfunction "7_7") (pintype "passive"))
      (node (ref "U$1") (pin "42") (pinfunction "IC1/RTCC/INT1/RD8_42") (pintype "passive"))
    )
    (net (code "26") (name "Net-(U$1-IC2{slash}*U1CTS{slash}INT2{slash}RD9)") (class "Default")
      (node (ref "JP3") (pin "1") (pinfunction "1_1") (pintype "passive"))
      (node (ref "SV8") (pin "6") (pinfunction "6_6") (pintype "passive"))
      (node (ref "U$1") (pin "43") (pinfunction "IC2/*U1CTS/INT2/RD9_43") (pintype "passive"))
    )
    (net (code "27") (name "Net-(U$1-IC3{slash}PMCS2{slash}INT3{slash}RD10)") (class "Default")
      (node (ref "JP1") (pin "1") (pinfunction "1_1") (pintype "passive"))
      (node (ref "SV8") (pin "5") (pinfunction "5_5") (pintype "passive"))
      (node (ref "U$1") (pin "44") (pinfunction "IC3/PMCS2/INT3/RD10_44") (pintype "passive"))
    )
    (net (code "28") (name "Net-(U$1-IC4{slash}PMCS1{slash}INT4{slash}RD11)") (class "Default")
      (node (ref "JP2") (pin "1") (pinfunction "1_1") (pintype "passive"))
      (node (ref "SV8") (pin "4") (pinfunction "4_4") (pintype "passive"))
      (node (ref "U$1") (pin "45") (pinfunction "IC4/PMCS1/INT4/RD11_45") (pintype "passive"))
    )
    (net (code "29") (name "Net-(U$1-OC1{slash}RD0)") (class "Default")
      (node (ref "SV8") (pin "3") (pinfunction "3_3") (pintype "passive"))
      (node (ref "U$1") (pin "46") (pinfunction "OC1/RD0_46") (pintype "passive"))
    )
    (net (code "30") (name "Net-(U$1-OC2{slash}RD1)") (class "Default")
      (node (ref "SV7") (pin "16") (pinfunction "16_16") (pintype "passive"))
      (node (ref "U$1") (pin "49") (pinfunction "OC2/RD1_49") (pintype "passive"))
      (node (ref "U$19") (pin "A6") (pinfunction "A6_A6") (pintype "bidirectional"))
    )
    (net (code "31") (name "Net-(U$1-OC3{slash}RD2)") (class "Default")
      (node (ref "SV7") (pin "15") (pinfunction "15_15") (pintype "passive"))
      (node (ref "U$1") (pin "50") (pinfunction "OC3/RD2_50") (pintype "passive"))
      (node (ref "U$19") (pin "A5") (pinfunction "A5_A5") (pintype "bidirectional"))
    )
    (net (code "32") (name "Net-(U$1-OSC1{slash}CLKI{slash}RC12)") (class "Default")
      (node (ref "SV8") (pin "10") (pinfunction "10_10") (pintype "passive"))
      (node (ref "U$1") (pin "39") (pinfunction "OSC1/CLKI/RC12_39") (pintype "passive"))
    )
    (net (code "33") (name "Net-(U$1-OSC2{slash}CLKO{slash}RC15)") (class "Default")
      (node (ref "SV8") (pin "9") (pinfunction "9_9") (pintype "passive"))
      (node (ref "U$1") (pin "40") (pinfunction "OSC2/CLKO/RC15_40") (pintype "passive"))
    )
    (net (code "34") (name "Net-(U$1-PGC1{slash}EMUC1{slash}VREF-{slash}AN1{slash}CN3{slash}RB1)") (class "Default")
      (node (ref "J3") (pin "5") (pinfunction "5_5") (pintype "passive"))
      (node (ref "SV5") (pin "15") (pinfunction "15_15") (pintype "passive"))
      (node (ref "U$1") (pin "15") (pinfunction "PGC1/EMUC1/VREF-/AN1/CN3/RB1_15") (pintype "passive"))
    )
    (net (code "35") (name "Net-(U$1-PGC2{slash}EMUC2{slash}AN6{slash}OCFA{slash}RB6)") (class "Default")
      (node (ref "SV6") (pin "1") (pinfunction "1_1") (pintype "passive"))
      (node (ref "U$1") (pin "17") (pinfunction "PGC2/EMUC2/AN6/OCFA/RB6_17") (pintype "passive"))
    )
    (net (code "36") (name "Net-(U$1-PGD1{slash}EMUD1{slash}PMA6{slash}VREF+{slash}AN0{slash}CN2{slash}RB0)") (class "Default")
      (node (ref "J3") (pin "4") (pinfunction "4_4") (pintype "passive"))
      (node (ref "SV5") (pin "16") (pinfunction "16_16") (pintype "passive"))
      (node (ref "U$1") (pin "16") (pinfunction "PGD1/EMUD1/PMA6/VREF+/AN0/CN2/RB0_16") (pintype "passive"))
    )
    (net (code "37") (name "Net-(U$1-PGD2{slash}EMUD2{slash}AN7{slash}RB7)") (class "Default")
      (node (ref "SV6") (pin "2") (pinfunction "2_2") (pintype "passive"))
      (node (ref "U$1") (pin "18") (pinfunction "PGD2/EMUD2/AN7/RB7_18") (pintype "passive"))
    )
    (net (code "38") (name "Net-(U$1-PMA0{slash}AN15{slash}OCFB{slash}CN12{slash}RB15)") (class "Default")
      (node (ref "RLED") (pin "1") (pinfunction "1_1") (pintype "passive"))
      (node (ref "SV6") (pin "14") (pinfunction "14_14") (pintype "passive"))
      (node (ref "U$1") (pin "30") (pinfunction "PMA0/AN15/OCFB/CN12/RB15_30") (pintype "passive"))
    )
    (net (code "39") (name "Net-(U$1-PMA1{slash}*U2RTS{slash}BCLK2{slash}AN14{slash}RB14)") (class "Default")
      (node (ref "SV6") (pin "13") (pinfunction "13_13") (pintype "passive"))
      (node (ref "U$1") (pin "29") (pinfunction "PMA1/*U2RTS/BCLK2/AN14/RB14_29") (pintype "passive"))
    )
    (net (code "40") (name "Net-(U$1-PMA2{slash}*SS2{slash}CN11{slash}RG9)") (class "Default")
      (node (ref "SV5") (pin "8") (pinfunction "8_8") (pintype "passive"))
      (node (ref "U$1") (pin "8") (pinfunction "PMA2/*SS2/CN11/RG9_8") (pintype "passive"))
    )
    (net (code "41") (name "Net-(U$1-PMA3{slash}SDO2{slash}CN10{slash}RG8)") (class "Default")
      (node (ref "SV5") (pin "6") (pinfunction "6_6") (pintype "passive"))
      (node (ref "U$1") (pin "6") (pinfunction "PMA3/SDO2/CN10/RG8_6") (pintype "passive"))
    )
    (net (code "42") (name "Net-(U$1-PMA4{slash}SDI2{slash}CN9{slash}RG7)") (class "Default")
      (node (ref "SV5") (pin "5") (pinfunction "5_5") (pintype "passive"))
      (node (ref "U$1") (pin "5") (pinfunction "PMA4/SDI2/CN9/RG7_5") (pintype "passive"))
    )
    (net (code "43") (name "Net-(U$1-PMA5{slash}SCK2{slash}CN8{slash}RG6)") (class "Default")
      (node (ref "SV5") (pin "4") (pinfunction "4_4") (pintype "passive"))
      (node (ref "U$1") (pin "4") (pinfunction "PMA5/SCK2/CN8/RG6_4") (pintype "passive"))
    )
    (net (code "44") (name "Net-(U$1-PMA8{slash}U2TX{slash}SCL2{slash}CN18{slash}RF5)") (class "Default")
      (node (ref "SV6") (pin "16") (pinfunction "16_16") (pintype "passive"))
      (node (ref "U$1") (pin "32") (pinfunction "PMA8/U2TX/SCL2/CN18/RF5_32") (pintype "passive"))
    )
    (net (code "45") (name "Net-(U$1-PMA9{slash}U2RX{slash}SDA2{slash}CN17{slash}RF4)") (class "Default")
      (node (ref "SV6") (pin "15") (pinfunction "15_15") (pintype "passive"))
      (node (ref "U$1") (pin "31") (pinfunction "PMA9/U2RX/SDA2/CN17/RF4_31") (pintype "passive"))
    )
    (net (code "46") (name "Net-(U$1-PMBE{slash}OC4{slash}RD3)") (class "Default")
      (node (ref "SV7") (pin "14") (pinfunction "14_14") (pintype "passive"))
      (node (ref "U$1") (pin "51") (pinfunction "PMBE/OC4/RD3_51") (pintype "passive"))
    )
    (net (code "47") (name "Net-(U$1-PMD0{slash}RE0)") (class "Default")
      (node (ref "SV7") (pin "5") (pinfunction "5_5") (pintype "passive"))
      (node (ref "U$1") (pin "60") (pinfunction "PMD0/RE0_60") (pintype "passive"))
    )
    (net (code "48") (name "Net-(U$1-PMD1{slash}RE1)") (class "Default")
      (node (ref "SV7") (pin "4") (pinfunction "4_4") (pintype "passive"))
      (node (ref "U$1") (pin "61") (pinfunction "PMD1/RE1_61") (pintype "passive"))
      (node (ref "U$19") (pin "A4") (pinfunction "A4_A4") (pintype "bidirectional"))
    )
    (net (code "49") (name "Net-(U$1-PMD2{slash}RE2)") (class "Default")
      (node (ref "SV7") (pin "3") (pinfunction "3_3") (pintype "passive"))
      (node (ref "U$1") (pin "62") (pinfunction "PMD2/RE2_62") (pintype "passive"))
      (node (ref "U$19") (pin "A3") (pinfunction "A3_A3") (pintype "bidirectional"))
    )
    (net (code "50") (name "Net-(U$1-PMD3{slash}RE3)") (class "Default")
      (node (ref "SV7") (pin "2") (pinfunction "2_2") (pintype "passive"))
      (node (ref "U$1") (pin "63") (pinfunction "PMD3/RE3_63") (pintype "passive"))
      (node (ref "U$19") (pin "A2") (pinfunction "A2_A2") (pintype "bidirectional"))
    )
    (net (code "51") (name "Net-(U$1-PMD4{slash}RE4)") (class "Default")
      (node (ref "SV7") (pin "1") (pinfunction "1_1") (pintype "passive"))
      (node (ref "U$1") (pin "64") (pinfunction "PMD4/RE4_64") (pintype "passive"))
      (node (ref "U$19") (pin "A1") (pinfunction "A1_A1") (pintype "bidirectional"))
    )
    (net (code "52") (name "Net-(U$1-PMD5{slash}RE5)") (class "Default")
      (node (ref "SV5") (pin "1") (pinfunction "1_1") (pintype "passive"))
      (node (ref "U$1") (pin "1") (pinfunction "PMD5/RE5_1") (pintype "passive"))
    )
    (net (code "53") (name "Net-(U$1-PMD6{slash}RE6)") (class "Default")
      (node (ref "SV5") (pin "2") (pinfunction "2_2") (pintype "passive"))
      (node (ref "U$1") (pin "2") (pinfunction "PMD6/RE6_2") (pintype "passive"))
    )
    (net (code "54") (name "Net-(U$1-PMD7{slash}RE7)") (class "Default")
      (node (ref "SV5") (pin "3") (pinfunction "3_3") (pintype "passive"))
      (node (ref "U$1") (pin "3") (pinfunction "PMD7/RE7_3") (pintype "passive"))
    )
    (net (code "55") (name "Net-(U$1-PMRD{slash}CN14{slash}RD5)") (class "Default")
      (node (ref "SV7") (pin "12") (pinfunction "12_12") (pintype "passive"))
      (node (ref "U$1") (pin "53") (pinfunction "PMRD/CN14/RD5_53") (pintype "passive"))
    )
    (net (code "56") (name "Net-(U$1-PMWR{slash}OC5{slash}IC5{slash}CN13{slash}RD4)") (class "Default")
      (node (ref "SV7") (pin "13") (pinfunction "13_13") (pintype "passive"))
      (node (ref "U$1") (pin "52") (pinfunction "PMWR/OC5/IC5/CN13/RD4_52") (pintype "passive"))
    )
    (net (code "57") (name "Net-(U$1-RF0)") (class "Default")
      (node (ref "SV7") (pin "7") (pinfunction "7_7") (pintype "passive"))
      (node (ref "U$1") (pin "58") (pinfunction "RF0_58") (pintype "passive"))
    )
    (net (code "58") (name "Net-(U$1-RF1)") (class "Default")
      (node (ref "SV7") (pin "6") (pinfunction "6_6") (pintype "passive"))
      (node (ref "U$1") (pin "59") (pinfunction "RF1_59") (pintype "passive"))
    )
    (net (code "59") (name "Net-(U$1-SOSCI{slash}CN1{slash}RC13)") (class "Default")
      (node (ref "SV8") (pin "2") (pinfunction "2_2") (pintype "passive"))
      (node (ref "U$1") (pin "47") (pinfunction "SOSCI/CN1/RC13_47") (pintype "passive"))
    )
    (net (code "60") (name "Net-(U$1-SOSCO{slash}T1CK{slash}CN0{slash}RC14)") (class "Default")
      (node (ref "SV8") (pin "1") (pinfunction "1_1") (pintype "passive"))
      (node (ref "U$1") (pin "48") (pinfunction "SOSCO/T1CK/CN0/RC14_48") (pintype "passive"))
    )
    (net (code "61") (name "Net-(U$1-TCK{slash}PMA11{slash}AN12{slash}RB12)") (class "Default")
      (node (ref "SV6") (pin "11") (pinfunction "11_11") (pintype "passive"))
      (node (ref "U$1") (pin "27") (pinfunction "TCK/PMA11/AN12/RB12_27") (pintype "passive"))
    )
    (net (code "62") (name "Net-(U$1-TDI{slash}PMA10{slash}AN13{slash}RB13)") (class "Default")
      (node (ref "SV6") (pin "12") (pinfunction "12_12") (pintype "passive"))
      (node (ref "U$1") (pin "28") (pinfunction "TDI/PMA10/AN13/RB13_28") (pintype "passive"))
    )
    (net (code "63") (name "Net-(U$1-TDO{slash}PMA12{slash}AN11{slash}RB11)") (class "Default")
      (node (ref "SV6") (pin "8") (pinfunction "8_8") (pintype "passive"))
      (node (ref "U$1") (pin "24") (pinfunction "TDO/PMA12/AN11/RB11_24") (pintype "passive"))
    )
    (net (code "64") (name "Net-(U$1-TMS{slash}PMA13{slash}CVREF{slash}AN10{slash}RB10)") (class "Default")
      (node (ref "SV6") (pin "7") (pinfunction "7_7") (pintype "passive"))
      (node (ref "U$1") (pin "23") (pinfunction "TMS/PMA13/CVREF/AN10/RB10_23") (pintype "passive"))
    )
    (net (code "65") (name "Net-(U$1-U1RX{slash}SDI1{slash}RF2)") (class "Default")
      (node (ref "SV8") (pin "15") (pinfunction "15_15") (pintype "passive"))
      (node (ref "U$1") (pin "34") (pinfunction "U1RX/SDI1/RF2_34") (pintype "passive"))
      (node (ref "U$19") (pin "A8") (pinfunction "A8_A8") (pintype "bidirectional"))
    )
    (net (code "66") (name "Net-(U$1-U1TX{slash}SDO1{slash}RF3)") (class "Default")
      (node (ref "SV8") (pin "16") (pinfunction "16_16") (pintype "passive"))
      (node (ref "U$1") (pin "33") (pinfunction "U1TX/SDO1/RF3_33") (pintype "passive"))
      (node (ref "U$19") (pin "A7") (pinfunction "A7_A7") (pintype "bidirectional"))
    )
    (net (code "67") (name "Net-(U$1-VCAP{slash}VDDCORE)") (class "Default")
      (node (ref "SV7") (pin "9") (pinfunction "9_9") (pintype "passive"))
      (node (ref "U$1") (pin "56") (pinfunction "VCAP/VDDCORE_56") (pintype "passive"))
      (node (ref "U$3") (pin "1") (pinfunction "1_1") (pintype "passive"))
    )
    (net (code "68") (name "Net-(U$4-BOOT)") (class "Default")
      (node (ref "CBOOT7") (pin "2") (pinfunction "2_2") (pintype "passive"))
      (node (ref "U$4") (pin "1") (pinfunction "BOOT_1") (pintype "bidirectional"))
    )
    (net (code "69") (name "Net-(U$4-VSENSE)") (class "Default")
      (node (ref "U$4") (pin "4") (pinfunction "VSENSE_4") (pintype "bidirectional"))
      (node (ref "U$8") (pin "1") (pinfunction "1_1") (pintype "passive"))
      (node (ref "U$9") (pin "2") (pinfunction "2_2") (pintype "passive"))
    )
    (net (code "70") (name "Net-(U$12-FB)") (class "Default")
      (node (ref "R1_5") (pin "2") (pinfunction "2_2") (pintype "passive"))
      (node (ref "R2_5") (pin "1") (pinfunction "1_1") (pintype "passive"))
      (node (ref "U$12") (pin "5") (pinfunction "FB_5") (pintype "bidirectional"))
    )
    (net (code "71") (name "Net-(U$12-PG)") (class "Default")
      (node (ref "U$12") (pin "8") (pinfunction "PG_8") (pintype "bidirectional"))
      (node (ref "U$16") (pin "2") (pinfunction "2_2") (pintype "passive"))
    )
    (net (code "72") (name "Net-(U$19-PadB1)") (class "Default")
      (node (ref "U$19") (pin "B1") (pinfunction "B1_B1") (pintype "bidirectional"))
      (node (ref "U$2") (pin "IN1") (pinfunction "IN1_IN1") (pintype "bidirectional"))
    )
    (net (code "73") (name "Net-(U$19-PadB2)") (class "Default")
      (node (ref "U$19") (pin "B2") (pinfunction "B2_B2") (pintype "bidirectional"))
      (node (ref "U$2") (pin "IN2") (pinfunction "IN2_IN2") (pintype "bidirectional"))
    )
    (net (code "74") (name "Net-(U$19-PadB3)") (class "Default")
      (node (ref "U$19") (pin "B3") (pinfunction "B3_B3") (pintype "bidirectional"))
      (node (ref "U$2") (pin "IN3") (pinfunction "IN3_IN3") (pintype "bidirectional"))
    )
    (net (code "75") (name "Net-(U$19-PadB4)") (class "Default")
      (node (ref "U$19") (pin "B4") (pinfunction "B4_B4") (pintype "bidirectional"))
      (node (ref "U$2") (pin "IN4") (pinfunction "IN4_IN4") (pintype "bidirectional"))
    )
    (net (code "76") (name "Net-(U$19-PadB5)") (class "Default")
      (node (ref "U$19") (pin "B5") (pinfunction "B5_B5") (pintype "bidirectional"))
      (node (ref "U$2") (pin "ENA") (pinfunction "ENA_ENA") (pintype "bidirectional"))
    )
    (net (code "77") (name "Net-(U$19-PadB6)") (class "Default")
      (node (ref "U$19") (pin "B6") (pinfunction "B6_B6") (pintype "bidirectional"))
      (node (ref "U$2") (pin "ENB") (pinfunction "ENB_ENB") (pintype "bidirectional"))
    )
    (net (code "78") (name "Net-(U$19-PadB7)") (class "Default")
      (node (ref "U$19") (pin "B7") (pinfunction "B7_B7") (pintype "bidirectional"))
      (node (ref "U$39") (pin "R1OUT") (pinfunction "R1OUT_R1OUT") (pintype "bidirectional"))
    )
    (net (code "79") (name "Net-(U$19-PadB8)") (class "Default")
      (node (ref "U$19") (pin "B8") (pinfunction "B8_B8") (pintype "bidirectional"))
      (node (ref "U$39") (pin "T1IN") (pinfunction "T1IN_T1IN") (pintype "bidirectional"))
    )
    (net (code "80") (name "Net-(U$19-PadOE)") (class "Default")
      (node (ref "U$19") (pin "OE") (pinfunction "OE_OE") (pintype "bidirectional"))
      (node (ref "U$20") (pin "1") (pinfunction "1_1") (pintype "passive"))
    )
    (net (code "81") (name "Net-(U$26-ADJ)") (class "Default")
      (node (ref "CADJ12") (pin "2") (pinfunction "2_2") (pintype "passive"))
      (node (ref "RAJ12") (pin "1") (pinfunction "1_1") (pintype "passive"))
      (node (ref "U$26") (pin "1") (pinfunction "ADJ_1") (pintype "bidirectional"))
    )
    (net (code "82") (name "Net-(U$26-FB)") (class "Default")
      (node (ref "U$26") (pin "3") (pinfunction "FB_3") (pintype "bidirectional"))
      (node (ref "U$35") (pin "2") (pinfunction "2_2") (pintype "passive"))
      (node (ref "U$36") (pin "1") (pinfunction "1_1") (pintype "passive"))
      (node (ref "U$37") (pin "2") (pinfunction "2_2") (pintype "passive"))
    )
    (net (code "83") (name "Net-(U$26-ISEN)") (class "Default")
      (node (ref "Q1") (pin "5") (pinfunction "D_5") (pintype "passive"))
      (node (ref "Q1") (pin "6") (pinfunction "D_6") (pintype "passive"))
      (node (ref "Q1") (pin "7") (pinfunction "D_7") (pintype "passive"))
      (node (ref "Q1") (pin "8") (pinfunction "D_8") (pintype "passive"))
      (node (ref "RSNS12") (pin "1") (pinfunction "1_1") (pintype "passive"))
      (node (ref "U$26") (pin "5") (pinfunction "ISEN_5") (pintype "bidirectional"))
    )
    (net (code "84") (name "Net-(U$26-RT)") (class "Default")
      (node (ref "RT12") (pin "1") (pinfunction "1_1") (pintype "passive"))
      (node (ref "U$26") (pin "2") (pinfunction "RT_2") (pintype "bidirectional"))
    )
    (net (code "85") (name "Net-(U$26-VCC)") (class "Default")
      (node (ref "CVCC12") (pin "2") (pinfunction "2_2") (pintype "passive"))
      (node (ref "U$26") (pin "7") (pinfunction "VCC_7") (pintype "bidirectional"))
    )
    (net (code "86") (name "Net-(U$39-CS-)") (class "Default")
      (node (ref "U$39") (pin "C2-") (pinfunction "C2-_C2-") (pintype "bidirectional"))
      (node (ref "U$39") (pin "C2-2") (pinfunction "CS-_C2-2") (pintype "bidirectional"))
    )
    (net (code "87") (name "Net-(U$39-PadC2+)") (class "Default")
      (node (ref "U$39") (pin "C2+") (pinfunction "C2+_C2+") (pintype "bidirectional"))
      (node (ref "U$39") (pin "C2+2") (pinfunction "C2+2_C2+2") (pintype "bidirectional"))
    )
    (net (code "88") (name "Net-(U$39-PadR1IN)") (class "Default")
      (node (ref "U$39") (pin "R1IN") (pinfunction "R1IN_R1IN") (pintype "bidirectional"))
      (node (ref "X4") (pin "3") (pinfunction "3_3") (pintype "passive"))
    )
    (net (code "89") (name "Net-(U$39-PadT1OUT)") (class "Default")
      (node (ref "U$39") (pin "T1OUT") (pinfunction "T1OUT_T1OUT") (pintype "bidirectional"))
      (node (ref "X4") (pin "2") (pinfunction "2_2") (pintype "passive"))
    )
    (net (code "90") (name "Net-(U$39-PadV-)") (class "Default")
      (node (ref "U$39") (pin "V-") (pinfunction "V-_V-") (pintype "bidirectional"))
      (node (ref "U$39") (pin "V-2") (pinfunction "V-2_V-2") (pintype "bidirectional"))
    )
    (net (code "91") (name "Net-(X10A-S)") (class "Default")
      (node (ref "D1") (pin "C") (pinfunction "C_C") (pintype "passive"))
      (node (ref "D7") (pin "A") (pinfunction "A_A") (pintype "passive"))
      (node (ref "U$2") (pin "OUT2") (pinfunction "OUT2_OUT2") (pintype "bidirectional"))
      (node (ref "X10") (pin "1") (pinfunction "S_1") (pintype "passive"))
    )
    (net (code "92") (name "Net-(X10B-S)") (class "Default")
      (node (ref "D2") (pin "C") (pinfunction "C_C") (pintype "passive"))
      (node (ref "D8") (pin "A") (pinfunction "A_A") (pintype "passive"))
      (node (ref "U$2") (pin "OUT1") (pinfunction "OUT1_OUT1") (pintype "bidirectional"))
      (node (ref "X10") (pin "2") (pinfunction "S_2") (pintype "passive"))
    )
    (net (code "93") (name "Net-(X10C-S)") (class "Default")
      (node (ref "D5") (pin "A") (pinfunction "A_A") (pintype "passive"))
      (node (ref "D6") (pin "C") (pinfunction "C_C") (pintype "passive"))
      (node (ref "U$2") (pin "OUT4") (pinfunction "OUT4_OUT4") (pintype "bidirectional"))
      (node (ref "X10") (pin "3") (pinfunction "S_3") (pintype "passive"))
    )
    (net (code "94") (name "Net-(X10D-S)") (class "Default")
      (node (ref "D3") (pin "C") (pinfunction "C_C") (pintype "passive"))
      (node (ref "D4") (pin "A") (pinfunction "A_A") (pintype "passive"))
      (node (ref "U$2") (pin "OUT3") (pinfunction "OUT3_OUT3") (pintype "bidirectional"))
      (node (ref "X10") (pin "4") (pinfunction "S_4") (pintype "passive"))
    )
    (net (code "95") (name "V+") (class "Default")
      (node (ref "C1") (pin "+") (pinfunction "+_+") (pintype "passive"))
      (node (ref "CADJ12") (pin "1") (pinfunction "1_1") (pintype "passive"))
      (node (ref "CIN12") (pin "1") (pinfunction "1_1") (pintype "passive"))
      (node (ref "CIN5") (pin "1") (pinfunction "1_1") (pintype "passive"))
      (node (ref "CIN7") (pin "1") (pinfunction "1_1") (pintype "passive"))
      (node (ref "CVCC12") (pin "1") (pinfunction "1_1") (pintype "passive"))
      (node (ref "J1") (pin "PWR") (pinfunction "PWR_PWR") (pintype "bidirectional"))
      (node (ref "RAJ12") (pin "2") (pinfunction "2_2") (pintype "passive"))
      (node (ref "RSNS12") (pin "2") (pinfunction "2_2") (pintype "passive"))
      (node (ref "RT12") (pin "2") (pinfunction "2_2") (pintype "passive"))
      (node (ref "U$12") (pin "2") (pinfunction "VIN_2") (pintype "bidirectional"))
      (node (ref "U$12") (pin "3") (pinfunction "EN_3") (pintype "bidirectional"))
      (node (ref "U$26") (pin "8") (pinfunction "VIN_8") (pintype "bidirectional"))
      (node (ref "U$4") (pin "7") (pinfunction "VIN_7") (pintype "bidirectional"))
    )
    (net (code "96") (name "unconnected-(J3-Pad6)") (class "Default")
      (node (ref "J3") (pin "6") (pinfunction "6_6") (pintype "passive"))
    )
    (net (code "97") (name "unconnected-(U$2-PadN.C.)") (class "Default")
      (node (ref "U$2") (pin "N.C.") (pinfunction "N.C._N.C.") (pintype "bidirectional"))
    )
    (net (code "98") (name "unconnected-(U$2-PadNC)") (class "Default")
      (node (ref "U$2") (pin "NC") (pinfunction "NC_NC") (pintype "bidirectional"))
    )
    (net (code "99") (name "unconnected-(U$4-ENA-Pad5)") (class "Default")
      (node (ref "U$4") (pin "5") (pinfunction "ENA_5") (pintype "bidirectional"))
    )
    (net (code "100") (name "unconnected-(U$39-PadC1+)") (class "Default")
      (node (ref "U$39") (pin "C1+") (pinfunction "C1+_C1+") (pintype "bidirectional"))
    )
    (net (code "101") (name "unconnected-(U$39-PadC1-)") (class "Default")
      (node (ref "U$39") (pin "C1-") (pinfunction "C1-_C1-") (pintype "bidirectional"))
    )
    (net (code "102") (name "unconnected-(U$39-PadR2IN)") (class "Default")
      (node (ref "U$39") (pin "R2IN") (pinfunction "R2IN_R2IN") (pintype "bidirectional"))
    )
    (net (code "103") (name "unconnected-(U$39-PadR2OUT)") (class "Default")
      (node (ref "U$39") (pin "R2OUT") (pinfunction "R2OUT_R2OUT") (pintype "bidirectional"))
    )
    (net (code "104") (name "unconnected-(U$39-PadT2IN)") (class "Default")
      (node (ref "U$39") (pin "T2IN") (pinfunction "T2IN_T2IN") (pintype "bidirectional"))
    )
    (net (code "105") (name "unconnected-(U$39-PadT2OUT)") (class "Default")
      (node (ref "U$39") (pin "T2OUT") (pinfunction "T2OUT_T2OUT") (pintype "bidirectional"))
    )
    (net (code "106") (name "unconnected-(U$39-PadV+)") (class "Default")
      (node (ref "U$39") (pin "V+") (pinfunction "V+_V+") (pintype "bidirectional"))
    )
    (net (code "107") (name "unconnected-(X4-Pad1)") (class "Default")
      (node (ref "X4") (pin "1") (pinfunction "1_1") (pintype "passive"))
    )
    (net (code "108") (name "unconnected-(X4-Pad4)") (class "Default")
      (node (ref "X4") (pin "4") (pinfunction "4_4") (pintype "passive"))
    )
    (net (code "109") (name "unconnected-(X4-Pad6)") (class "Default")
      (node (ref "X4") (pin "6") (pinfunction "6_6") (pintype "passive"))
    )
    (net (code "110") (name "unconnected-(X4-Pad7)") (class "Default")
      (node (ref "X4") (pin "7") (pinfunction "7_7") (pintype "passive"))
    )
    (net (code "111") (name "unconnected-(X4-Pad8)") (class "Default")
      (node (ref "X4") (pin "8") (pinfunction "8_8") (pintype "passive"))
    )
    (net (code "112") (name "unconnected-(X4-Pad9)") (class "Default")
      (node (ref "X4") (pin "9") (pinfunction "9_9") (pintype "passive"))
    )
  )
)
